# Sheet1.net
KiCad netlist of a schematic drawn in Altium Designer
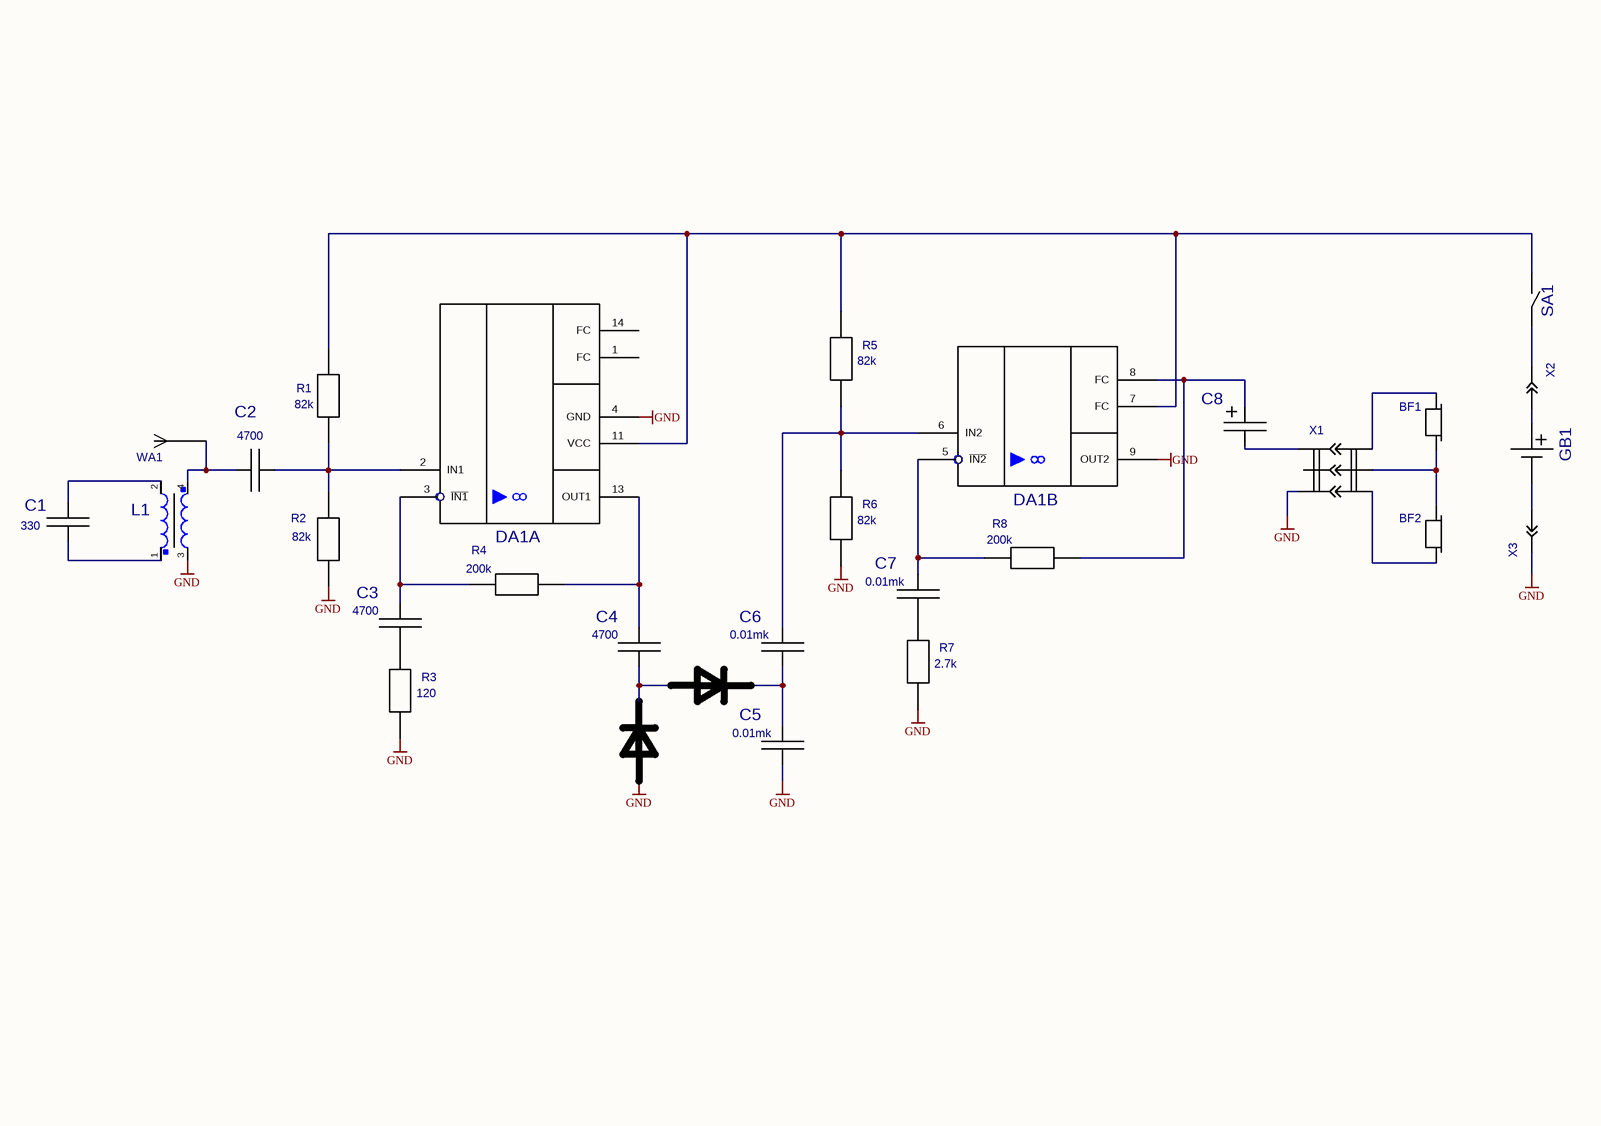
[diagram p0: Sheet1.SCHDOC]

(export (version "E")
  (design (tool "Eeschema 10.0.6"))
  (components
    (comp (ref "BF1") (value "BF") (footprint "BF") (libsource (lib "*") (part "BF")))
    (comp (ref "BF2") (value "BF") (footprint "BF") (libsource (lib "*") (part "BF")))
    (comp (ref "C1")
      (value "330")
      (footprint "1017-B3R")
      (description "1017-B3R")
      (libsource (lib "*") (part "1017-B3R"))
    )
    (comp (ref "C2")
      (value "4700")
      (footprint "1017-B3R")
      (description "1017-B3R")
      (libsource (lib "*") (part "1017-B3R"))
    )
    (comp (ref "C3")
      (value "4700")
      (footprint "1017-B3R")
      (description "1017-B3R")
      (libsource (lib "*") (part "1017-B3R"))
    )
    (comp (ref "C4")
      (value "4700")
      (footprint "1017-B3R")
      (description "1017-B3R")
      (libsource (lib "*") (part "1017-B3R"))
    )
    (comp (ref "C5")
      (value "0.01mk")
      (footprint "1017-B3R")
      (description "1017-B3R")
      (libsource (lib "*") (part "1017-B3R"))
    )
    (comp (ref "C6")
      (value "0.01mk")
      (footprint "1017-B3R")
      (description "1017-B3R")
      (libsource (lib "*") (part "1017-B3R"))
    )
    (comp (ref "C7")
      (value "0.01mk")
      (footprint "1017-B3R")
      (description "1017-B3R")
      (libsource (lib "*") (part "1017-B3R"))
    )
    (comp (ref "C8") (value "CE3528-B") (footprint "CE3528-B") (libsource (lib "*") (part "CE3528-B")))
    (comp (ref "DA1")
      (value "К157УД2")
      (footprint "DIP-14_MM")
      (fields (field (name "AUTHOR") "pcbdesigner.ru"))
      (libsource (lib "*") (part "К157УД2"))
    )
    (comp (ref "GB1")
      (value "BH023(CR2032)_SMD")
      (footprint "BH023(CR2032)_SMD")
      (fields (field (name "AUTHOR") "pcbdesigner.ru"))
      (libsource (lib "*") (part "BH023(CR2032)_SMD"))
    )
    (comp (ref "L1")
      (value "B82722A")
      (footprint "B82722A")
      (fields (field (name "AUTHOR") "pcbdesigner.ru"))
      (libsource (lib "*") (part "B82722A"))
    )
    (comp (ref "R1")
      (value "82k")
      (footprint "R100")
      (description "R100")
      (libsource (lib "*") (part "R100"))
    )
    (comp (ref "R2")
      (value "82k")
      (footprint "R100")
      (description "R100")
      (libsource (lib "*") (part "R100"))
    )
    (comp (ref "R3")
      (value "120")
      (footprint "R100")
      (description "R100")
      (libsource (lib "*") (part "R100"))
    )
    (comp (ref "R4")
      (value "200k")
      (footprint "R100")
      (description "R100")
      (libsource (lib "*") (part "R100"))
    )
    (comp (ref "R5")
      (value "82k")
      (footprint "R100")
      (description "R100")
      (libsource (lib "*") (part "R100"))
    )
    (comp (ref "R6")
      (value "82k")
      (footprint "R100")
      (description "R100")
      (libsource (lib "*") (part "R100"))
    )
    (comp (ref "R7")
      (value "2.7k")
      (footprint "R100")
      (description "R100")
      (libsource (lib "*") (part "R100"))
    )
    (comp (ref "R8")
      (value "200k")
      (footprint "R100")
      (description "R100")
      (libsource (lib "*") (part "R100"))
    )
    (comp (ref "SA1")
      (value "8AS9M2RE")
      (footprint "8AS9M2RE")
      (fields (field (name "AUTHOR") "pcbdesigner.ru"))
      (libsource (lib "*") (part "8AS9M2RE"))
    )
    (comp (ref "VD1") (value "1N34") (footprint "DO-7") (libsource (lib "*") (part "1N34")))
    (comp (ref "VD2") (value "1N34") (footprint "DO-7") (libsource (lib "*") (part "1N34")))
    (comp (ref "WA1")
      (value "TELESKOP_ANTENNA")
      (footprint "TELESKOP_ANTENNA")
      (fields (field (name "AUTHOR") "pcbdesigner.ru"))
      (libsource (lib "*") (part "TELESKOP_ANTENNA"))
    )
    (comp (ref "X1") (value "X3") (footprint "X3") (libsource (lib "*") (part "X3")))
    (comp (ref "X2") (value "X") (footprint "X") (libsource (lib "*") (part "X")))
    (comp (ref "X3") (value "X") (footprint "X") (libsource (lib "*") (part "X")))
  )
  (nets
    (net (code "1") (name "GND") (class "Default")
      (node (ref "C5") (pin "1") (pinfunction "I/OA_1") (pintype "passive"))
      (node (ref "DA1") (pin "4") (pinfunction "GND_4") (pintype "passive"))
      (node (ref "DA1") (pin "9") (pinfunction "OUT2_9") (pintype "passive"))
      (node (ref "L1") (pin "3") (pinfunction "3_3") (pintype "passive"))
      (node (ref "R2") (pin "1") (pintype "passive"))
      (node (ref "R3") (pin "2") (pintype "passive"))
      (node (ref "R6") (pin "2") (pintype "passive"))
      (node (ref "R7") (pin "2") (pintype "passive"))
      (node (ref "VD1") (pin "A") (pinfunction "A_A") (pintype "passive"))
      (node (ref "X1") (pin "5") (pintype "passive"))
      (node (ref "X3") (pin "1") (pintype "passive"))
    )
    (net (code "2") (name "Net-(BF1-Pad1)") (class "Default")
      (node (ref "BF1") (pin "1") (pintype "passive"))
      (node (ref "BF2") (pin "2") (pintype "passive"))
      (node (ref "X1") (pin "3") (pintype "passive"))
    )
    (net (code "3") (name "Net-(BF1-Pad2)") (class "Default")
      (node (ref "BF1") (pin "2") (pintype "passive"))
      (node (ref "X1") (pin "2") (pintype "passive"))
    )
    (net (code "4") (name "Net-(BF2-Pad1)") (class "Default")
      (node (ref "BF2") (pin "1") (pintype "passive"))
      (node (ref "X1") (pin "4") (pintype "passive"))
    )
    (net (code "5") (name "Net-(C1-I{slash}OA)") (class "Default")
      (node (ref "C1") (pin "1") (pinfunction "I/OA_1") (pintype "passive"))
      (node (ref "L1") (pin "2") (pinfunction "2_2") (pintype "passive"))
    )
    (net (code "6") (name "Net-(C1-I{slash}OB)") (class "Default")
      (node (ref "C1") (pin "2") (pinfunction "I/OB_2") (pintype "passive"))
      (node (ref "L1") (pin "1") (pinfunction "1_1") (pintype "passive"))
    )
    (net (code "7") (name "Net-(C2-I{slash}OA)") (class "Default")
      (node (ref "C2") (pin "1") (pinfunction "I/OA_1") (pintype "passive"))
      (node (ref "L1") (pin "4") (pinfunction "4_4") (pintype "passive"))
      (node (ref "WA1") (pin "1") (pinfunction "1_1") (pintype "passive"))
    )
    (net (code "8") (name "Net-(C2-I{slash}OB)") (class "Default")
      (node (ref "C2") (pin "2") (pinfunction "I/OB_2") (pintype "passive"))
      (node (ref "DA1") (pin "2") (pinfunction "IN1_2") (pintype "passive"))
      (node (ref "R1") (pin "1") (pintype "passive"))
      (node (ref "R2") (pin "2") (pintype "passive"))
    )
    (net (code "9") (name "Net-(C3-I{slash}OA)") (class "Default")
      (node (ref "C3") (pin "1") (pinfunction "I/OA_1") (pintype "passive"))
      (node (ref "R3") (pin "1") (pintype "passive"))
    )
    (net (code "10") (name "Net-(C3-I{slash}OB)") (class "Default")
      (node (ref "C3") (pin "2") (pinfunction "I/OB_2") (pintype "passive"))
      (node (ref "DA1") (pin "3") (pinfunction "~{IN1}_3") (pintype "passive"))
      (node (ref "R4") (pin "1") (pintype "passive"))
    )
    (net (code "11") (name "Net-(C4-I{slash}OA)") (class "Default")
      (node (ref "C4") (pin "1") (pinfunction "I/OA_1") (pintype "passive"))
      (node (ref "VD1") (pin "K") (pinfunction "K_K") (pintype "passive"))
      (node (ref "VD2") (pin "A") (pinfunction "A_A") (pintype "passive"))
    )
    (net (code "12") (name "Net-(C4-I{slash}OB)") (class "Default")
      (node (ref "C4") (pin "2") (pinfunction "I/OB_2") (pintype "passive"))
      (node (ref "DA1") (pin "13") (pinfunction "OUT1_13") (pintype "passive"))
      (node (ref "R4") (pin "2") (pintype "passive"))
    )
    (net (code "13") (name "Net-(C5-I{slash}OB)") (class "Default")
      (node (ref "C5") (pin "2") (pinfunction "I/OB_2") (pintype "passive"))
      (node (ref "C6") (pin "1") (pinfunction "I/OA_1") (pintype "passive"))
      (node (ref "VD2") (pin "K") (pinfunction "K_K") (pintype "passive"))
    )
    (net (code "14") (name "Net-(C6-I{slash}OB)") (class "Default")
      (node (ref "C6") (pin "2") (pinfunction "I/OB_2") (pintype "passive"))
      (node (ref "DA1") (pin "6") (pinfunction "IN2_6") (pintype "passive"))
      (node (ref "R5") (pin "2") (pintype "passive"))
      (node (ref "R6") (pin "1") (pintype "passive"))
    )
    (net (code "15") (name "Net-(C7-I{slash}OA)") (class "Default")
      (node (ref "C7") (pin "1") (pinfunction "I/OA_1") (pintype "passive"))
      (node (ref "R7") (pin "1") (pintype "passive"))
    )
    (net (code "16") (name "Net-(C7-I{slash}OB)") (class "Default")
      (node (ref "C7") (pin "2") (pinfunction "I/OB_2") (pintype "passive"))
      (node (ref "DA1") (pin "5") (pinfunction "~{IN2}_5") (pintype "passive"))
      (node (ref "R8") (pin "1") (pintype "passive"))
    )
    (net (code "17") (name "Net-(C8-i{slash}o)") (class "Default")
      (node (ref "C8") (pin "1") (pinfunction "i/o_1") (pintype "passive"))
      (node (ref "DA1") (pin "8") (pinfunction "FC_8") (pintype "passive"))
      (node (ref "R8") (pin "2") (pintype "passive"))
    )
    (net (code "18") (name "Net-(C8-i{slash}o1)") (class "Default")
      (node (ref "C8") (pin "2") (pinfunction "i/o1_2") (pintype "passive"))
      (node (ref "X1") (pin "1") (pintype "passive"))
    )
    (net (code "19") (name "Net-(DA1A-VCC)") (class "Default")
      (node (ref "DA1") (pin "11") (pinfunction "VCC_11") (pintype "passive"))
      (node (ref "DA1") (pin "7") (pinfunction "FC_7") (pintype "passive"))
      (node (ref "R1") (pin "2") (pintype "passive"))
      (node (ref "R5") (pin "1") (pintype "passive"))
      (node (ref "SA1") (pin "1") (pinfunction "1_1") (pintype "passive"))
    )
    (net (code "20") (name "Net-(GB1-Pad1)") (class "Default")
      (node (ref "GB1") (pin "1") (pinfunction "1_1") (pintype "passive"))
      (node (ref "X3") (pin "2") (pintype "passive"))
    )
    (net (code "21") (name "Net-(GB1-Pad2)") (class "Default")
      (node (ref "GB1") (pin "2") (pinfunction "2_2") (pintype "passive"))
      (node (ref "X2") (pin "2") (pintype "passive"))
    )
    (net (code "22") (name "Net-(SA1-Pad2)") (class "Default")
      (node (ref "SA1") (pin "2") (pinfunction "2_2") (pintype "passive"))
      (node (ref "X2") (pin "1") (pintype "passive"))
    )
    (net (code "23") (name "unconnected-(DA1-Pad10)") (class "Default")
      (node (ref "DA1") (pin "10") (pintype "passive"))
    )
    (net (code "24") (name "unconnected-(DA1-Pad10)_1") (class "Default")
      (node (ref "DA1") (pin "10") (pintype "passive"))
    )
    (net (code "25") (name "unconnected-(DA1-Pad12)") (class "Default")
      (node (ref "DA1") (pin "12") (pintype "passive"))
    )
    (net (code "26") (name "unconnected-(DA1-Pad12)_1") (class "Default")
      (node (ref "DA1") (pin "12") (pintype "passive"))
    )
    (net (code "27") (name "unconnected-(DA1A-FC-Pad1)") (class "Default")
      (node (ref "DA1") (pin "1") (pinfunction "FC_1") (pintype "passive"))
    )
    (net (code "28") (name "unconnected-(DA1A-FC-Pad14)") (class "Default")
      (node (ref "DA1") (pin "14") (pinfunction "FC_14") (pintype "passive"))
    )
  )
)
